# Joystick.net
KiCad netlist of a schematic drawn in EAGLE
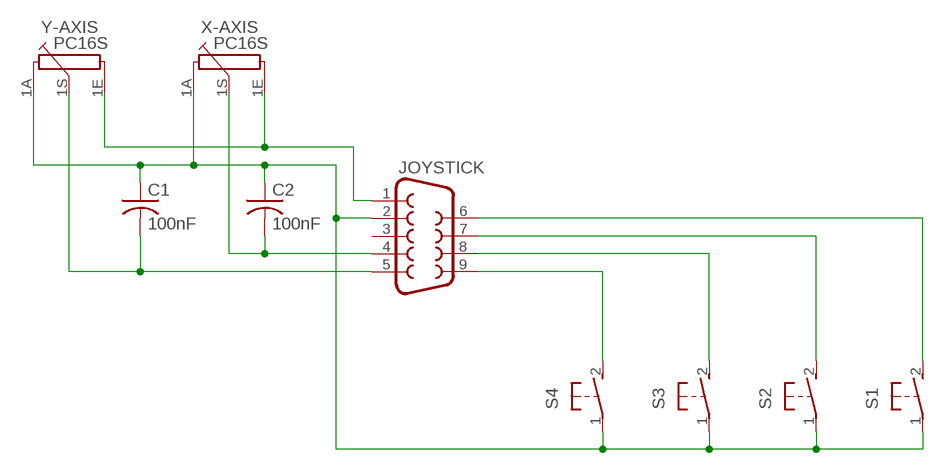
[diagram p0: schematic, sheet 1]

(export (version "E")
  (design (tool "Eeschema 10.0.6"))
  (components
    (comp (ref "C1")
      (value "100nF")
      (footprint "eagle-import:C050-025X075")
      (libsource (lib "eagle-import") (part "C-US050-025X075"))
    )
    (comp (ref "C2")
      (value "100nF")
      (footprint "eagle-import:C050-025X075")
      (libsource (lib "eagle-import") (part "C-US050-025X075"))
    )
    (comp (ref "JOYSTICK")
      (value "F09V")
      (footprint "eagle-import:F09V")
      (libsource (lib "eagle-import") (part "F09V"))
    )
    (comp (ref "S1")
      (value "31-XX")
      (footprint "eagle-import:B3F-31XX")
      (fields (field (name "MPN") "B3F-3100"))
      (libsource (lib "eagle-import") (part "31-XX"))
    )
    (comp (ref "S2")
      (value "31-XX")
      (footprint "eagle-import:B3F-31XX")
      (fields (field (name "MPN") "B3F-3100"))
      (libsource (lib "eagle-import") (part "31-XX"))
    )
    (comp (ref "S3")
      (value "31-XX")
      (footprint "eagle-import:B3F-31XX")
      (fields (field (name "MPN") "B3F-3100"))
      (libsource (lib "eagle-import") (part "31-XX"))
    )
    (comp (ref "S4")
      (value "31-XX")
      (footprint "eagle-import:B3F-31XX")
      (fields (field (name "MPN") "B3F-3100"))
      (libsource (lib "eagle-import") (part "31-XX"))
    )
    (comp (ref "X-AXIS")
      (value "PC16S")
      (footprint "eagle-import:PC16S")
      (libsource (lib "eagle-import") (part "PC16S"))
    )
    (comp (ref "Y-AXIS")
      (value "PC16S")
      (footprint "eagle-import:PC16S")
      (libsource (lib "eagle-import") (part "PC16S"))
    )
  )
  (nets
    (net (code "1") (name "Net-(C1-Pad2)") (class "Default")
      (node (ref "C1") (pin "2") (pinfunction "2_2") (pintype "passive"))
      (node (ref "JOYSTICK") (pin "5") (pinfunction "5_5") (pintype "passive"))
      (node (ref "Y-AXIS") (pin "1S") (pinfunction "1S_1S") (pintype "passive"))
    )
    (net (code "2") (name "Net-(C2-Pad2)") (class "Default")
      (node (ref "C2") (pin "2") (pinfunction "2_2") (pintype "passive"))
      (node (ref "JOYSTICK") (pin "4") (pinfunction "4_4") (pintype "passive"))
      (node (ref "X-AXIS") (pin "1S") (pinfunction "1S_1S") (pintype "passive"))
    )
    (net (code "3") (name "Net-(JOYSTICK-Pad1)") (class "Default")
      (node (ref "JOYSTICK") (pin "1") (pinfunction "1_1") (pintype "passive"))
      (node (ref "X-AXIS") (pin "1E") (pinfunction "1E_1E") (pintype "passive"))
      (node (ref "Y-AXIS") (pin "1E") (pinfunction "1E_1E") (pintype "passive"))
    )
    (net (code "4") (name "Net-(S1-P)") (class "Default")
      (node (ref "C1") (pin "1") (pinfunction "1_1") (pintype "passive"))
      (node (ref "C2") (pin "1") (pinfunction "1_1") (pintype "passive"))
      (node (ref "JOYSTICK") (pin "2") (pinfunction "2_2") (pintype "passive"))
      (node (ref "S1") (pin "1") (pinfunction "P_1") (pintype "passive"))
      (node (ref "S2") (pin "1") (pinfunction "P_1") (pintype "passive"))
      (node (ref "S3") (pin "1") (pinfunction "P_1") (pintype "passive"))
      (node (ref "S4") (pin "1") (pinfunction "P_1") (pintype "passive"))
      (node (ref "X-AXIS") (pin "1A") (pinfunction "1A_1A") (pintype "passive"))
      (node (ref "Y-AXIS") (pin "1A") (pinfunction "1A_1A") (pintype "passive"))
    )
    (net (code "5") (name "Net-(S1-S)") (class "Default")
      (node (ref "JOYSTICK") (pin "6") (pinfunction "6_6") (pintype "passive"))
      (node (ref "S1") (pin "2") (pinfunction "S_2") (pintype "passive"))
    )
    (net (code "6") (name "Net-(S2-S)") (class "Default")
      (node (ref "JOYSTICK") (pin "7") (pinfunction "7_7") (pintype "passive"))
      (node (ref "S2") (pin "2") (pinfunction "S_2") (pintype "passive"))
    )
    (net (code "7") (name "Net-(S3-S)") (class "Default")
      (node (ref "JOYSTICK") (pin "8") (pinfunction "8_8") (pintype "passive"))
      (node (ref "S3") (pin "2") (pinfunction "S_2") (pintype "passive"))
    )
    (net (code "8") (name "Net-(S4-S)") (class "Default")
      (node (ref "JOYSTICK") (pin "9") (pinfunction "9_9") (pintype "passive"))
      (node (ref "S4") (pin "2") (pinfunction "S_2") (pintype "passive"))
    )
    (net (code "9") (name "unconnected-(JOYSTICK-Pad3)") (class "Default")
      (node (ref "JOYSTICK") (pin "3") (pinfunction "3_3") (pintype "passive"))
    )
  )
)
